# Copter_Receiver.net
KiCad netlist of a schematic drawn in EAGLE
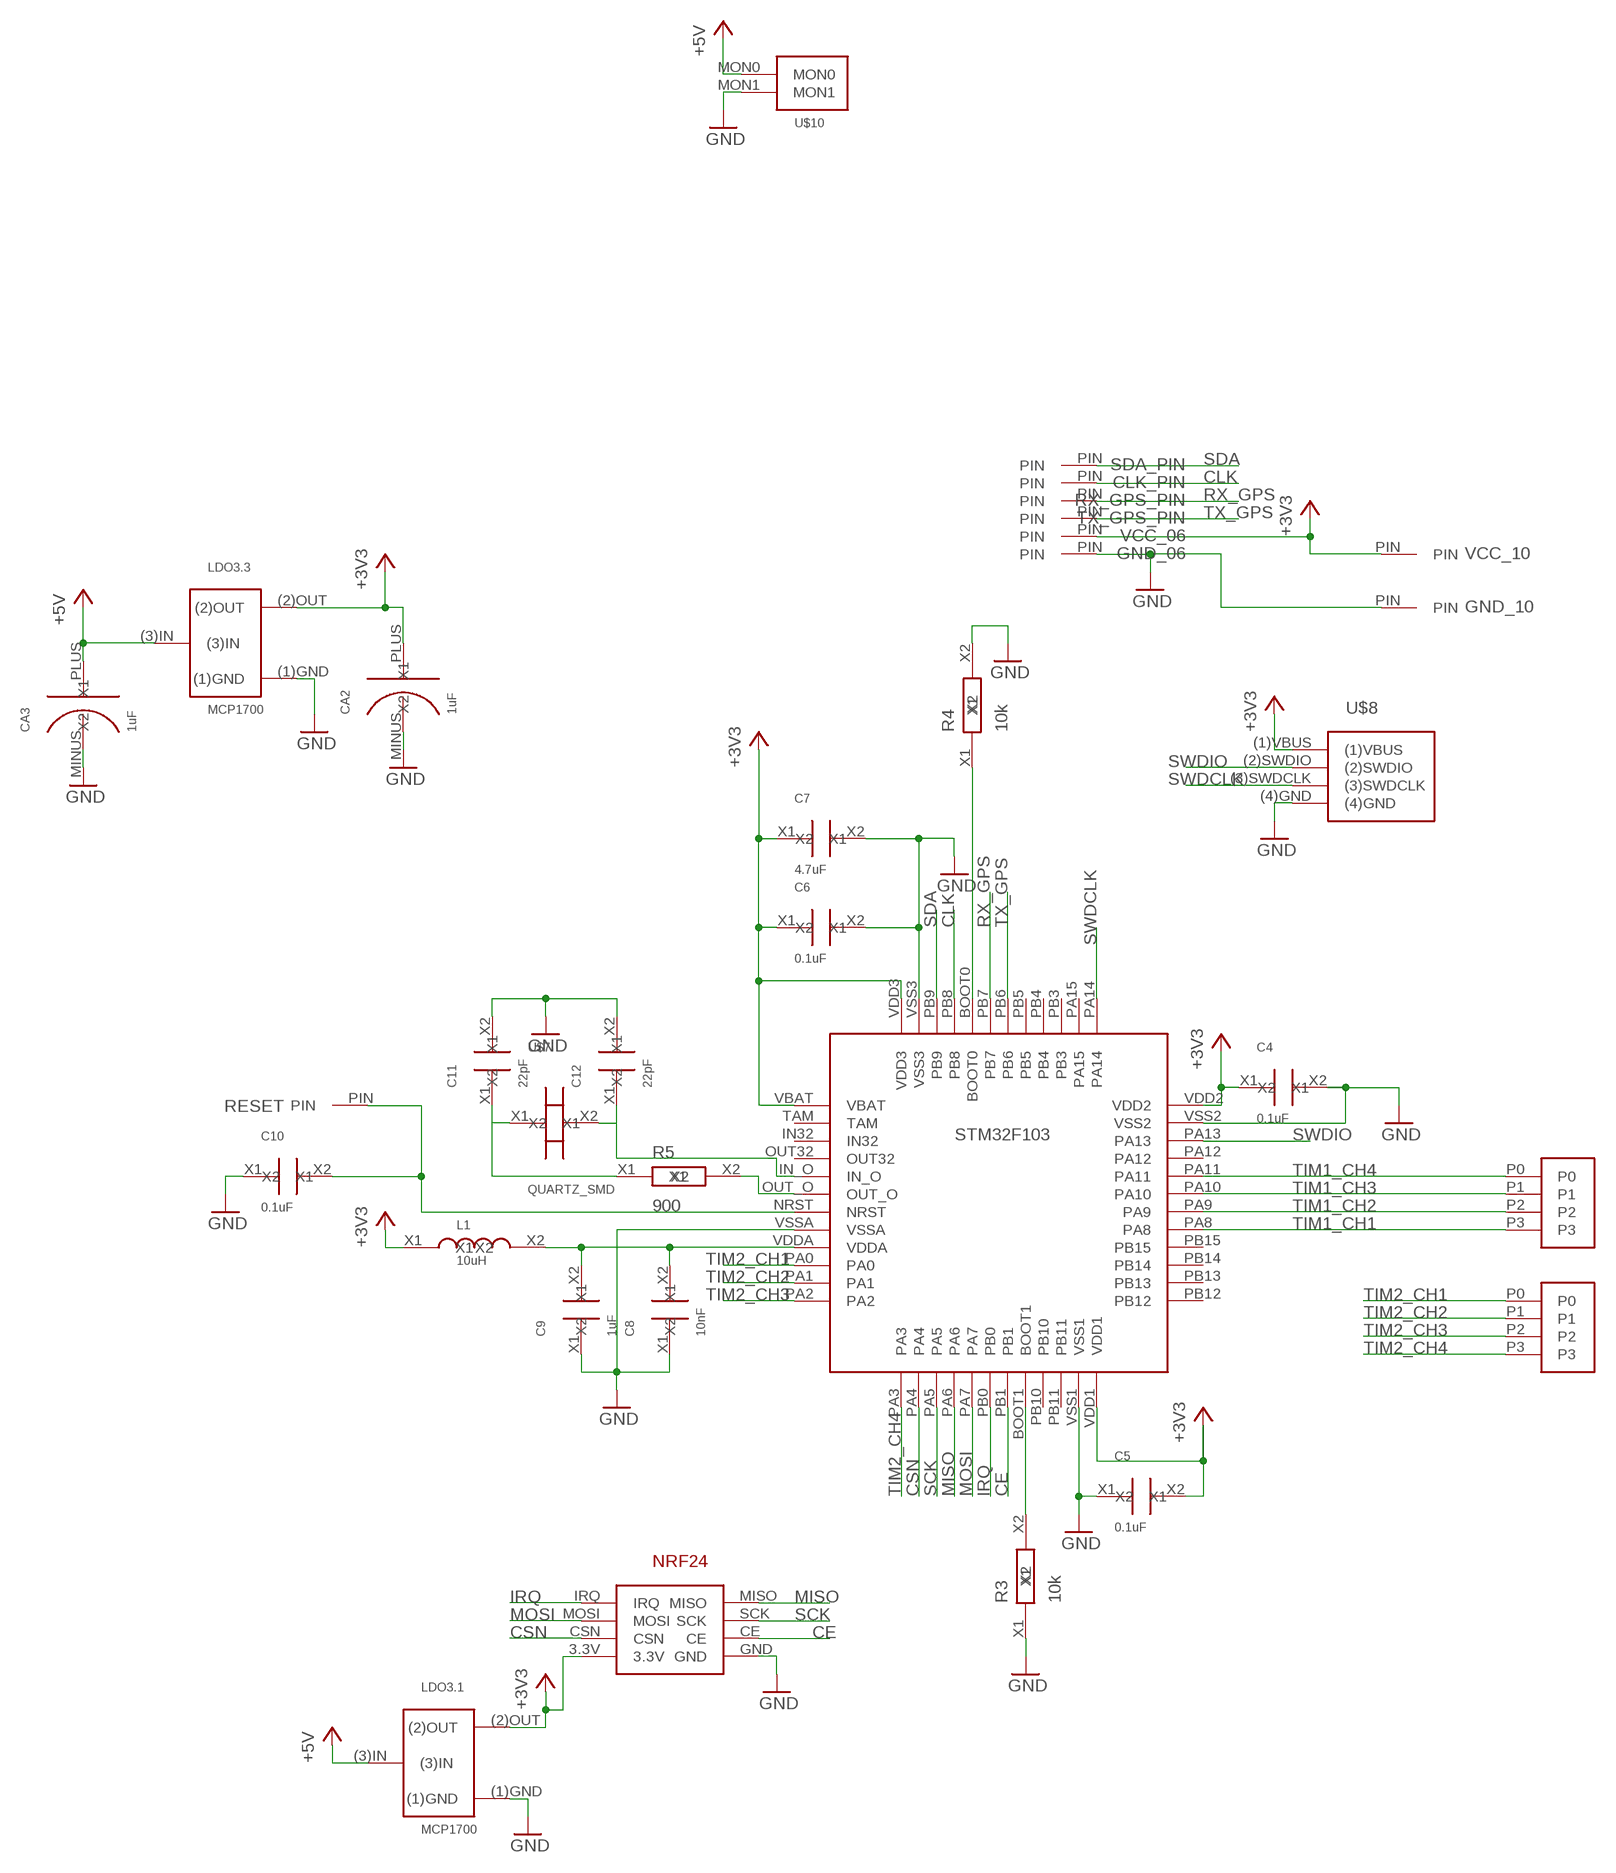
[diagram p0: schematic, sheet 1]

(export (version "E")
  (design (tool "Eeschema 10.0.6"))
  (components
    (comp (ref "C4")
      (value "0.1uF")
      (footprint "eagle-import:SMD_2.1X1.25")
      (libsource (lib "eagle-import") (part "C_SMD_2.1X1.25"))
    )
    (comp (ref "C5")
      (value "0.1uF")
      (footprint "eagle-import:SMD_2.1X1.25")
      (libsource (lib "eagle-import") (part "C_SMD_2.1X1.25"))
    )
    (comp (ref "C6")
      (value "0.1uF")
      (footprint "eagle-import:SMD_2.1X1.25")
      (libsource (lib "eagle-import") (part "C_SMD_2.1X1.25"))
    )
    (comp (ref "C7")
      (value "4.7uF")
      (footprint "eagle-import:SMD_2.1X1.25")
      (libsource (lib "eagle-import") (part "C_SMD_2.1X1.25"))
    )
    (comp (ref "C8")
      (value "10nF")
      (footprint "eagle-import:SMD_2.1X1.25")
      (libsource (lib "eagle-import") (part "C_SMD_2.1X1.25"))
    )
    (comp (ref "C9")
      (value "1uF")
      (footprint "eagle-import:SMD_2.1X1.25")
      (libsource (lib "eagle-import") (part "C_SMD_2.1X1.25"))
    )
    (comp (ref "C10")
      (value "0.1uF")
      (footprint "eagle-import:SMD_2.1X1.25")
      (libsource (lib "eagle-import") (part "C_SMD_2.1X1.25"))
    )
    (comp (ref "C11")
      (value "22pF")
      (footprint "eagle-import:SMD_2.1X1.25")
      (libsource (lib "eagle-import") (part "C_SMD_2.1X1.25"))
    )
    (comp (ref "C12")
      (value "22pF")
      (footprint "eagle-import:SMD_2.1X1.25")
      (libsource (lib "eagle-import") (part "C_SMD_2.1X1.25"))
    )
    (comp (ref "CA2")
      (value "1uF")
      (footprint "eagle-import:C_SMD_TA_A")
      (libsource (lib "eagle-import") (part "C_SMD_TA_A"))
    )
    (comp (ref "CA3")
      (value "1uF")
      (footprint "eagle-import:C_SMD_TA_A")
      (libsource (lib "eagle-import") (part "C_SMD_TA_A"))
    )
    (comp (ref "CLK_PIN")
      (value "PIN_06")
      (footprint "eagle-import:PIN_06")
      (libsource (lib "eagle-import") (part "PIN_06"))
    )
    (comp (ref "GND_06")
      (value "PIN_06")
      (footprint "eagle-import:PIN_06")
      (libsource (lib "eagle-import") (part "PIN_06"))
    )
    (comp (ref "GND_10")
      (value "PIN")
      (footprint "eagle-import:PIN")
      (libsource (lib "eagle-import") (part "PIN"))
    )
    (comp (ref "L1")
      (value "10uH")
      (footprint "eagle-import:SMD_2.1X1.25")
      (libsource (lib "eagle-import") (part "L_SMD_2.1X1.25"))
    )
    (comp (ref "LDO3.1")
      (value "MCP1700")
      (footprint "eagle-import:MCP1700")
      (libsource (lib "eagle-import") (part "MCP1700"))
    )
    (comp (ref "LDO3.3")
      (value "MCP1700")
      (footprint "eagle-import:MCP1700")
      (libsource (lib "eagle-import") (part "MCP1700"))
    )
    (comp (ref "R3")
      (value "10k")
      (footprint "eagle-import:SMD_2.1X1.25")
      (libsource (lib "eagle-import") (part "R_SMD_2.1X1.25"))
    )
    (comp (ref "R4")
      (value "10k")
      (footprint "eagle-import:SMD_2.1X1.25")
      (libsource (lib "eagle-import") (part "R_SMD_2.1X1.25"))
    )
    (comp (ref "R5")
      (value "900")
      (footprint "eagle-import:SMD_2.1X1.25")
      (libsource (lib "eagle-import") (part "R_SMD_2.1X1.25"))
    )
    (comp (ref "RESET")
      (value "PIN")
      (footprint "eagle-import:PIN")
      (libsource (lib "eagle-import") (part "PIN"))
    )
    (comp (ref "RX_GPS_PIN")
      (value "PIN_06")
      (footprint "eagle-import:PIN_06")
      (libsource (lib "eagle-import") (part "PIN_06"))
    )
    (comp (ref "SDA_PIN")
      (value "PIN_06")
      (footprint "eagle-import:PIN_06")
      (libsource (lib "eagle-import") (part "PIN_06"))
    )
    (comp (ref "STM32F103")
      (value "STM32F103CBT6")
      (footprint "eagle-import:STM32F103CBT6")
      (libsource (lib "eagle-import") (part "STM32F103CBT6"))
    )
    (comp (ref "TX_GPS_PIN")
      (value "PIN_06")
      (footprint "eagle-import:PIN_06")
      (libsource (lib "eagle-import") (part "PIN_06"))
    )
    (comp (ref "U$1")
      (value "4PIN")
      (footprint "eagle-import:4PIN")
      (libsource (lib "eagle-import") (part "4PIN"))
    )
    (comp (ref "U$2")
      (value "NRF24_PLUG")
      (footprint "eagle-import:NRF24_PLUG")
      (libsource (lib "eagle-import") (part "NRF24_PLUG"))
    )
    (comp (ref "U$3")
      (value "4PIN")
      (footprint "eagle-import:4PIN")
      (libsource (lib "eagle-import") (part "4PIN"))
    )
    (comp (ref "U$7")
      (value "QUARTZ_SMD")
      (footprint "eagle-import:QUARTZ_SMD")
      (libsource (lib "eagle-import") (part "QUARTZ_SMD"))
    )
    (comp (ref "U$8")
      (value "SWD")
      (footprint "eagle-import:SWD")
      (libsource (lib "eagle-import") (part "SWD"))
    )
    (comp (ref "U$10")
      (value "MON2PIN")
      (footprint "eagle-import:MON2PIN")
      (libsource (lib "eagle-import") (part "MON2PIN"))
    )
    (comp (ref "VCC_06")
      (value "PIN_06")
      (footprint "eagle-import:PIN_06")
      (libsource (lib "eagle-import") (part "PIN_06"))
    )
    (comp (ref "VCC_10")
      (value "PIN")
      (footprint "eagle-import:PIN")
      (libsource (lib "eagle-import") (part "PIN"))
    )
  )
  (nets
    (net (code "1") (name "+3V3") (class "Default")
      (node (ref "C4") (pin "X1") (pinfunction "X1_X1") (pintype "bidirectional"))
      (node (ref "C5") (pin "X2") (pinfunction "X2_X2") (pintype "bidirectional"))
      (node (ref "C6") (pin "X1") (pinfunction "X1_X1") (pintype "bidirectional"))
      (node (ref "C7") (pin "X1") (pinfunction "X1_X1") (pintype "bidirectional"))
      (node (ref "CA2") (pin "PLUS") (pinfunction "X2_PLUS") (pintype "bidirectional"))
      (node (ref "L1") (pin "X1") (pinfunction "X1_X1") (pintype "bidirectional"))
      (node (ref "LDO3.1") (pin "(2)OUT") (pinfunction "(2)OUT_(2)OUT") (pintype "bidirectional"))
      (node (ref "LDO3.3") (pin "(2)OUT") (pinfunction "(2)OUT_(2)OUT") (pintype "bidirectional"))
      (node (ref "STM32F103") (pin "VBAT") (pinfunction "VBAT_VBAT") (pintype "bidirectional"))
      (node (ref "STM32F103") (pin "VDD1") (pinfunction "VDD1_VDD1") (pintype "bidirectional"))
      (node (ref "STM32F103") (pin "VDD2") (pinfunction "VDD2_VDD2") (pintype "bidirectional"))
      (node (ref "STM32F103") (pin "VDD3") (pinfunction "VDD3_VDD3") (pintype "bidirectional"))
      (node (ref "U$2") (pin "3.3V") (pinfunction "3.3V_3.3V") (pintype "bidirectional"))
      (node (ref "U$8") (pin "(1)VBUS") (pinfunction "(1)VBUS_(1)VBUS") (pintype "bidirectional"))
      (node (ref "VCC_06") (pin "PIN") (pinfunction "PIN_PIN") (pintype "bidirectional"))
      (node (ref "VCC_10") (pin "PIN") (pinfunction "PIN_PIN") (pintype "bidirectional"))
    )
    (net (code "2") (name "+5V") (class "Default")
      (node (ref "CA3") (pin "PLUS") (pinfunction "X2_PLUS") (pintype "bidirectional"))
      (node (ref "LDO3.1") (pin "(3)IN") (pinfunction "(3)IN_(3)IN") (pintype "bidirectional"))
      (node (ref "LDO3.3") (pin "(3)IN") (pinfunction "(3)IN_(3)IN") (pintype "bidirectional"))
      (node (ref "U$10") (pin "MON0") (pinfunction "MON0_MON0") (pintype "bidirectional"))
    )
    (net (code "3") (name "/CE") (class "Default")
      (node (ref "STM32F103") (pin "PB1") (pinfunction "PB1_PB1") (pintype "bidirectional"))
      (node (ref "U$2") (pin "CE") (pinfunction "CE_CE") (pintype "bidirectional"))
    )
    (net (code "4") (name "/CLK") (class "Default")
      (node (ref "CLK_PIN") (pin "PIN") (pinfunction "PIN_PIN") (pintype "bidirectional"))
      (node (ref "STM32F103") (pin "PB8") (pinfunction "PB8_PB8") (pintype "bidirectional"))
    )
    (net (code "5") (name "/CSN") (class "Default")
      (node (ref "STM32F103") (pin "PA4") (pinfunction "PA4_PA4") (pintype "bidirectional"))
      (node (ref "U$2") (pin "CSN") (pinfunction "CSN_CSN") (pintype "bidirectional"))
    )
    (net (code "6") (name "/IRQ") (class "Default")
      (node (ref "STM32F103") (pin "PB0") (pinfunction "PB0_PB0") (pintype "bidirectional"))
      (node (ref "U$2") (pin "IRQ") (pinfunction "IRQ_IRQ") (pintype "bidirectional"))
    )
    (net (code "7") (name "/MISO") (class "Default")
      (node (ref "STM32F103") (pin "PA6") (pinfunction "PA6_PA6") (pintype "bidirectional"))
      (node (ref "U$2") (pin "MISO") (pinfunction "MISO_MISO") (pintype "bidirectional"))
    )
    (net (code "8") (name "/MOSI") (class "Default")
      (node (ref "STM32F103") (pin "PA7") (pinfunction "PA7_PA7") (pintype "bidirectional"))
      (node (ref "U$2") (pin "MOSI") (pinfunction "MOSI_MOSI") (pintype "bidirectional"))
    )
    (net (code "9") (name "/RX_GPS") (class "Default")
      (node (ref "RX_GPS_PIN") (pin "PIN") (pinfunction "PIN_PIN") (pintype "bidirectional"))
      (node (ref "STM32F103") (pin "PB7") (pinfunction "PB7_PB7") (pintype "bidirectional"))
    )
    (net (code "10") (name "/SCK") (class "Default")
      (node (ref "STM32F103") (pin "PA5") (pinfunction "PA5_PA5") (pintype "bidirectional"))
      (node (ref "U$2") (pin "SCK") (pinfunction "SCK_SCK") (pintype "bidirectional"))
    )
    (net (code "11") (name "/SDA") (class "Default")
      (node (ref "SDA_PIN") (pin "PIN") (pinfunction "PIN_PIN") (pintype "bidirectional"))
      (node (ref "STM32F103") (pin "PB9") (pinfunction "PB9_PB9") (pintype "bidirectional"))
    )
    (net (code "12") (name "/SWDCLK") (class "Default")
      (node (ref "STM32F103") (pin "PA14") (pinfunction "PA14_PA14") (pintype "bidirectional"))
      (node (ref "U$8") (pin "(3)SWDCLK") (pinfunction "(3)SWDCLK_(3)SWDCLK") (pintype "bidirectional"))
    )
    (net (code "13") (name "/SWDIO") (class "Default")
      (node (ref "STM32F103") (pin "PA13") (pinfunction "PA13_PA13") (pintype "bidirectional"))
      (node (ref "U$8") (pin "(2)SWDIO") (pinfunction "(2)SWDIO_(2)SWDIO") (pintype "bidirectional"))
    )
    (net (code "14") (name "/TIM1_CH1") (class "Default")
      (node (ref "STM32F103") (pin "PA8") (pinfunction "PA8_PA8") (pintype "bidirectional"))
      (node (ref "U$1") (pin "P3") (pinfunction "P3_P3") (pintype "bidirectional"))
    )
    (net (code "15") (name "/TIM1_CH2") (class "Default")
      (node (ref "STM32F103") (pin "PA9") (pinfunction "PA9_PA9") (pintype "bidirectional"))
      (node (ref "U$1") (pin "P2") (pinfunction "P2_P2") (pintype "bidirectional"))
    )
    (net (code "16") (name "/TIM1_CH3") (class "Default")
      (node (ref "STM32F103") (pin "PA10") (pinfunction "PA10_PA10") (pintype "bidirectional"))
      (node (ref "U$1") (pin "P1") (pinfunction "P1_P1") (pintype "bidirectional"))
    )
    (net (code "17") (name "/TIM1_CH4") (class "Default")
      (node (ref "STM32F103") (pin "PA11") (pinfunction "PA11_PA11") (pintype "bidirectional"))
      (node (ref "U$1") (pin "P0") (pinfunction "P0_P0") (pintype "bidirectional"))
    )
    (net (code "18") (name "/TIM2_CH1") (class "Default")
      (node (ref "STM32F103") (pin "PA0") (pinfunction "PA0_PA0") (pintype "bidirectional"))
      (node (ref "U$3") (pin "P0") (pinfunction "P0_P0") (pintype "bidirectional"))
    )
    (net (code "19") (name "/TIM2_CH2") (class "Default")
      (node (ref "STM32F103") (pin "PA1") (pinfunction "PA1_PA1") (pintype "bidirectional"))
      (node (ref "U$3") (pin "P1") (pinfunction "P1_P1") (pintype "bidirectional"))
    )
    (net (code "20") (name "/TIM2_CH3") (class "Default")
      (node (ref "STM32F103") (pin "PA2") (pinfunction "PA2_PA2") (pintype "bidirectional"))
      (node (ref "U$3") (pin "P2") (pinfunction "P2_P2") (pintype "bidirectional"))
    )
    (net (code "21") (name "/TIM2_CH4") (class "Default")
      (node (ref "STM32F103") (pin "PA3") (pinfunction "PA3_PA3") (pintype "bidirectional"))
      (node (ref "U$3") (pin "P3") (pinfunction "P3_P3") (pintype "bidirectional"))
    )
    (net (code "22") (name "/TX_GPS") (class "Default")
      (node (ref "STM32F103") (pin "PB6") (pinfunction "PB6_PB6") (pintype "bidirectional"))
      (node (ref "TX_GPS_PIN") (pin "PIN") (pinfunction "PIN_PIN") (pintype "bidirectional"))
    )
    (net (code "23") (name "GND") (class "Default")
      (node (ref "C10") (pin "X1") (pinfunction "X1_X1") (pintype "bidirectional"))
      (node (ref "C11") (pin "X2") (pinfunction "X2_X2") (pintype "bidirectional"))
      (node (ref "C12") (pin "X2") (pinfunction "X2_X2") (pintype "bidirectional"))
      (node (ref "C4") (pin "X2") (pinfunction "X2_X2") (pintype "bidirectional"))
      (node (ref "C5") (pin "X1") (pinfunction "X1_X1") (pintype "bidirectional"))
      (node (ref "C6") (pin "X2") (pinfunction "X2_X2") (pintype "bidirectional"))
      (node (ref "C7") (pin "X2") (pinfunction "X2_X2") (pintype "bidirectional"))
      (node (ref "C8") (pin "X1") (pinfunction "X1_X1") (pintype "bidirectional"))
      (node (ref "C9") (pin "X1") (pinfunction "X1_X1") (pintype "bidirectional"))
      (node (ref "CA2") (pin "MINUS") (pinfunction "X1_MINUS") (pintype "bidirectional"))
      (node (ref "CA3") (pin "MINUS") (pinfunction "X1_MINUS") (pintype "bidirectional"))
      (node (ref "GND_06") (pin "PIN") (pinfunction "PIN_PIN") (pintype "bidirectional"))
      (node (ref "GND_10") (pin "PIN") (pinfunction "PIN_PIN") (pintype "bidirectional"))
      (node (ref "LDO3.1") (pin "(1)GND") (pinfunction "(1)GND_(1)GND") (pintype "bidirectional"))
      (node (ref "LDO3.3") (pin "(1)GND") (pinfunction "(1)GND_(1)GND") (pintype "bidirectional"))
      (node (ref "R3") (pin "X1") (pinfunction "X1_X1") (pintype "bidirectional"))
      (node (ref "R4") (pin "X2") (pinfunction "X2_X2") (pintype "bidirectional"))
      (node (ref "STM32F103") (pin "VSS1") (pinfunction "VSS1_VSS1") (pintype "bidirectional"))
      (node (ref "STM32F103") (pin "VSS2") (pinfunction "VSS2_VSS2") (pintype "bidirectional"))
      (node (ref "STM32F103") (pin "VSS3") (pinfunction "VSS3_VSS3") (pintype "bidirectional"))
      (node (ref "STM32F103") (pin "VSSA") (pinfunction "VSSA_VSSA") (pintype "bidirectional"))
      (node (ref "U$10") (pin "MON1") (pinfunction "MON1_MON1") (pintype "bidirectional"))
      (node (ref "U$2") (pin "GND") (pinfunction "GND_GND") (pintype "bidirectional"))
      (node (ref "U$8") (pin "(4)GND") (pinfunction "(4)GND_(4)GND") (pintype "bidirectional"))
    )
    (net (code "24") (name "Net-(C8-PadX2)") (class "Default")
      (node (ref "C8") (pin "X2") (pinfunction "X2_X2") (pintype "bidirectional"))
      (node (ref "C9") (pin "X2") (pinfunction "X2_X2") (pintype "bidirectional"))
      (node (ref "L1") (pin "X2") (pinfunction "X2_X2") (pintype "bidirectional"))
      (node (ref "STM32F103") (pin "VDDA") (pinfunction "VDDA_VDDA") (pintype "bidirectional"))
    )
    (net (code "25") (name "Net-(C10-PadX2)") (class "Default")
      (node (ref "C10") (pin "X2") (pinfunction "X2_X2") (pintype "bidirectional"))
      (node (ref "RESET") (pin "PIN") (pinfunction "PIN_PIN") (pintype "bidirectional"))
      (node (ref "STM32F103") (pin "NRST") (pinfunction "NRST_NRST") (pintype "bidirectional"))
    )
    (net (code "26") (name "Net-(C11-PadX1)") (class "Default")
      (node (ref "C11") (pin "X1") (pinfunction "X1_X1") (pintype "bidirectional"))
      (node (ref "R5") (pin "X1") (pinfunction "X1_X1") (pintype "bidirectional"))
      (node (ref "U$7") (pin "X1") (pinfunction "X1_X1") (pintype "bidirectional"))
    )
    (net (code "27") (name "Net-(C12-PadX1)") (class "Default")
      (node (ref "C12") (pin "X1") (pinfunction "X1_X1") (pintype "bidirectional"))
      (node (ref "STM32F103") (pin "IN_O") (pinfunction "IN_O_IN_O") (pintype "bidirectional"))
      (node (ref "U$7") (pin "X2") (pinfunction "X2_X2") (pintype "bidirectional"))
    )
    (net (code "28") (name "Net-(R3-PadX2)") (class "Default")
      (node (ref "R3") (pin "X2") (pinfunction "X2_X2") (pintype "bidirectional"))
      (node (ref "STM32F103") (pin "BOOT1") (pinfunction "BOOT1_BOOT1") (pintype "bidirectional"))
    )
    (net (code "29") (name "Net-(R4-PadX1)") (class "Default")
      (node (ref "R4") (pin "X1") (pinfunction "X1_X1") (pintype "bidirectional"))
      (node (ref "STM32F103") (pin "BOOT0") (pinfunction "BOOT0_BOOT0") (pintype "bidirectional"))
    )
    (net (code "30") (name "Net-(R5-PadX2)") (class "Default")
      (node (ref "R5") (pin "X2") (pinfunction "X2_X2") (pintype "bidirectional"))
      (node (ref "STM32F103") (pin "OUT_O") (pinfunction "OUT_O_OUT_O") (pintype "bidirectional"))
    )
    (net (code "31") (name "unconnected-(STM32F103-PadIN32)") (class "Default")
      (node (ref "STM32F103") (pin "IN32") (pinfunction "IN32_IN32") (pintype "bidirectional"))
    )
    (net (code "32") (name "unconnected-(STM32F103-PadOUT32)") (class "Default")
      (node (ref "STM32F103") (pin "OUT32") (pinfunction "OUT32_OUT32") (pintype "bidirectional"))
    )
    (net (code "33") (name "unconnected-(STM32F103-PadPA12)") (class "Default")
      (node (ref "STM32F103") (pin "PA12") (pinfunction "PA12_PA12") (pintype "bidirectional"))
    )
    (net (code "34") (name "unconnected-(STM32F103-PadPA15)") (class "Default")
      (node (ref "STM32F103") (pin "PA15") (pinfunction "PA15_PA15") (pintype "bidirectional"))
    )
    (net (code "35") (name "unconnected-(STM32F103-PadPB3)") (class "Default")
      (node (ref "STM32F103") (pin "PB3") (pinfunction "PB3_PB3") (pintype "bidirectional"))
    )
    (net (code "36") (name "unconnected-(STM32F103-PadPB4)") (class "Default")
      (node (ref "STM32F103") (pin "PB4") (pinfunction "PB4_PB4") (pintype "bidirectional"))
    )
    (net (code "37") (name "unconnected-(STM32F103-PadPB5)") (class "Default")
      (node (ref "STM32F103") (pin "PB5") (pinfunction "PB5_PB5") (pintype "bidirectional"))
    )
    (net (code "38") (name "unconnected-(STM32F103-PadPB10)") (class "Default")
      (node (ref "STM32F103") (pin "PB10") (pinfunction "PB10_PB10") (pintype "bidirectional"))
    )
    (net (code "39") (name "unconnected-(STM32F103-PadPB11)") (class "Default")
      (node (ref "STM32F103") (pin "PB11") (pinfunction "PB11_PB11") (pintype "bidirectional"))
    )
    (net (code "40") (name "unconnected-(STM32F103-PadPB12)") (class "Default")
      (node (ref "STM32F103") (pin "PB12") (pinfunction "PB12_PB12") (pintype "bidirectional"))
    )
    (net (code "41") (name "unconnected-(STM32F103-PadPB13)") (class "Default")
      (node (ref "STM32F103") (pin "PB13") (pinfunction "PB13_PB13") (pintype "bidirectional"))
    )
    (net (code "42") (name "unconnected-(STM32F103-PadPB14)") (class "Default")
      (node (ref "STM32F103") (pin "PB14") (pinfunction "PB14_PB14") (pintype "bidirectional"))
    )
    (net (code "43") (name "unconnected-(STM32F103-PadPB15)") (class "Default")
      (node (ref "STM32F103") (pin "PB15") (pinfunction "PB15_PB15") (pintype "bidirectional"))
    )
    (net (code "44") (name "unconnected-(STM32F103-PadTAM)") (class "Default")
      (node (ref "STM32F103") (pin "TAM") (pinfunction "TAM_TAM") (pintype "bidirectional"))
    )
  )
)
